# V1_Layout.net
KiCad netlist of a schematic drawn in EAGLE
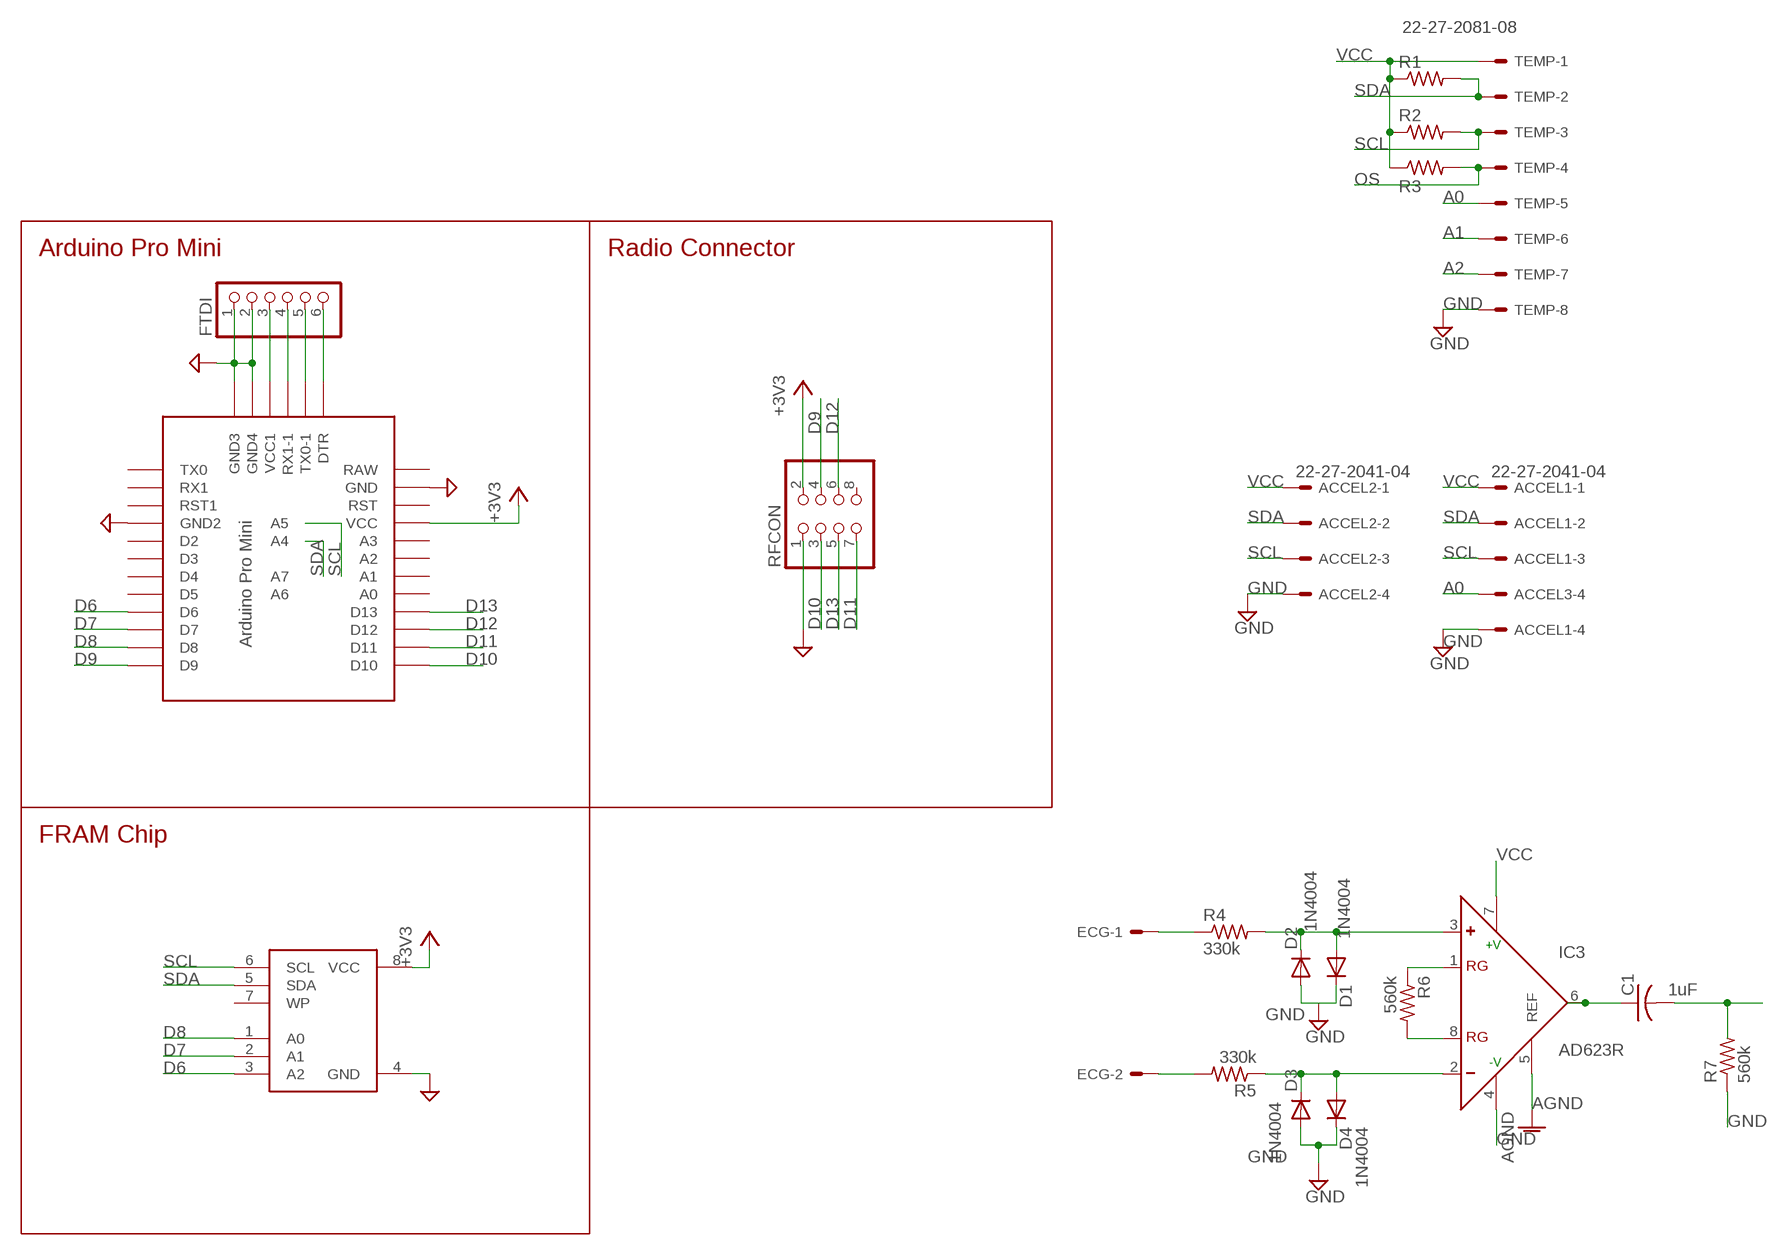
[diagram p0: schematic, sheet 1]

(export (version "E")
  (design (tool "Eeschema 10.0.6"))
  (components
    (comp (ref "ACCEL1")
      (value "22-27-2041-04")
      (footprint "eagle-import:6410-04")
      (fields (field (name "MF") "MOLEX"))
      (libsource (lib "eagle-import") (part "22-?-0427-2041"))
    )
    (comp (ref "ACCEL2")
      (value "22-27-2041-04")
      (footprint "eagle-import:6410-04")
      (fields (field (name "MF") "MOLEX"))
      (libsource (lib "eagle-import") (part "22-?-0427-2041"))
    )
    (comp (ref "ACCEL3")
      (value "22-27-2041-04")
      (footprint "eagle-import:6410-04")
      (fields (field (name "MF") "MOLEX"))
      (libsource (lib "eagle-import") (part "22-?-0427-2041"))
    )
    (comp (ref "C1")
      (value "1uF")
      (footprint "eagle-import:C0805")
      (libsource (lib "eagle-import") (part "C-USC0805"))
    )
    (comp (ref "D1")
      (value "1N4004")
      (footprint "eagle-import:DO41-10")
      (libsource (lib "eagle-import") (part "1N4004"))
    )
    (comp (ref "D2")
      (value "1N4004")
      (footprint "eagle-import:DO41-10")
      (libsource (lib "eagle-import") (part "1N4004"))
    )
    (comp (ref "D3")
      (value "1N4004")
      (footprint "eagle-import:DO41-10")
      (libsource (lib "eagle-import") (part "1N4004"))
    )
    (comp (ref "D4")
      (value "1N4004")
      (footprint "eagle-import:DO41-10")
      (libsource (lib "eagle-import") (part "1N4004"))
    )
    (comp (ref "ECG")
      (value "22-27-2021-02")
      (footprint "eagle-import:6410-02")
      (fields (field (name "MF") "MOLEX"))
      (libsource (lib "eagle-import") (part "22-?-0227-2021"))
    )
    (comp (ref "FTDI")
      (value "PINHD-1X6")
      (footprint "eagle-import:1X06")
      (libsource (lib "eagle-import") (part "PINHD-1X6"))
    )
    (comp (ref "IC3")
      (value "AD623R")
      (footprint "eagle-import:SO8")
      (fields (field (name "MPN") "AD623ARZ."))
      (libsource (lib "eagle-import") (part "AD623R"))
    )
    (comp (ref "R1")
      (value "R-US_R0805")
      (footprint "eagle-import:R0805")
      (libsource (lib "eagle-import") (part "R-US_R0805"))
    )
    (comp (ref "R2")
      (value "R-US_R0805")
      (footprint "eagle-import:R0805")
      (libsource (lib "eagle-import") (part "R-US_R0805"))
    )
    (comp (ref "R3")
      (value "R-US_R0805")
      (footprint "eagle-import:R0805")
      (libsource (lib "eagle-import") (part "R-US_R0805"))
    )
    (comp (ref "R4")
      (value "330k")
      (footprint "eagle-import:R0805")
      (libsource (lib "eagle-import") (part "R-US_R0805"))
    )
    (comp (ref "R5")
      (value "330k")
      (footprint "eagle-import:R0805")
      (libsource (lib "eagle-import") (part "R-US_R0805"))
    )
    (comp (ref "R6")
      (value "560k")
      (footprint "eagle-import:R0805")
      (libsource (lib "eagle-import") (part "R-US_R0805"))
    )
    (comp (ref "R7")
      (value "560k")
      (footprint "eagle-import:R0805")
      (libsource (lib "eagle-import") (part "R-US_R0805"))
    )
    (comp (ref "RFCON")
      (value "PINHD-2X4")
      (footprint "eagle-import:2X04")
      (libsource (lib "eagle-import") (part "PINHD-2X4"))
    )
    (comp (ref "TEMP")
      (value "22-27-2081-08")
      (footprint "eagle-import:6410-08")
      (fields (field (name "MF") "MOLEX"))
      (libsource (lib "eagle-import") (part "22-?-0827-2081"))
    )
    (comp (ref "U$1")
      (value "PRO-MINI-2")
      (footprint "eagle-import:PRO-MINI-2")
      (libsource (lib "eagle-import") (part "PRO-MINI-2"))
    )
    (comp (ref "U2")
      (value "MB85RC256VPF-G-JNERE2")
      (footprint "eagle-import:SOIC8")
      (libsource (lib "eagle-import") (part "MB85RC256VPF-G-JNERE2"))
    )
  )
  (nets
    (net (code "1") (name "+3V3") (class "Default")
      (node (ref "RFCON") (pin "2") (pinfunction "2_2") (pintype "passive"))
      (node (ref "U$1") (pin "VCC") (pinfunction "VCC_VCC") (pintype "bidirectional"))
      (node (ref "U2") (pin "8") (pinfunction "VCC_8") (pintype "bidirectional"))
    )
    (net (code "2") (name "/A0") (class "Default")
      (node (ref "ACCEL3") (pin "4") (pinfunction "S_4") (pintype "passive"))
      (node (ref "TEMP") (pin "5") (pinfunction "S_5") (pintype "passive"))
    )
    (net (code "3") (name "/A1") (class "Default")
      (node (ref "TEMP") (pin "6") (pinfunction "S_6") (pintype "passive"))
    )
    (net (code "4") (name "/A2") (class "Default")
      (node (ref "TEMP") (pin "7") (pinfunction "S_7") (pintype "passive"))
    )
    (net (code "5") (name "/D6") (class "Default")
      (node (ref "U$1") (pin "D6") (pinfunction "D6_D6") (pintype "bidirectional"))
      (node (ref "U2") (pin "3") (pinfunction "A2_3") (pintype "bidirectional"))
    )
    (net (code "6") (name "/D7") (class "Default")
      (node (ref "U$1") (pin "D7") (pinfunction "D7_D7") (pintype "bidirectional"))
      (node (ref "U2") (pin "2") (pinfunction "A1_2") (pintype "bidirectional"))
    )
    (net (code "7") (name "/D8") (class "Default")
      (node (ref "U$1") (pin "D8") (pinfunction "D8_D8") (pintype "bidirectional"))
      (node (ref "U2") (pin "1") (pinfunction "A0_1") (pintype "bidirectional"))
    )
    (net (code "8") (name "/D9") (class "Default")
      (node (ref "RFCON") (pin "4") (pinfunction "4_4") (pintype "passive"))
      (node (ref "U$1") (pin "D9") (pinfunction "D9_D9") (pintype "bidirectional"))
    )
    (net (code "9") (name "/D10") (class "Default")
      (node (ref "RFCON") (pin "3") (pinfunction "3_3") (pintype "passive"))
      (node (ref "U$1") (pin "D10") (pinfunction "D10_D10") (pintype "bidirectional"))
    )
    (net (code "10") (name "/D11") (class "Default")
      (node (ref "RFCON") (pin "7") (pinfunction "7_7") (pintype "passive"))
      (node (ref "U$1") (pin "D11") (pinfunction "D11_D11") (pintype "bidirectional"))
    )
    (net (code "11") (name "/D12") (class "Default")
      (node (ref "RFCON") (pin "6") (pinfunction "6_6") (pintype "passive"))
      (node (ref "U$1") (pin "D12") (pinfunction "D12_D12") (pintype "bidirectional"))
    )
    (net (code "12") (name "/D13") (class "Default")
      (node (ref "RFCON") (pin "5") (pinfunction "5_5") (pintype "passive"))
      (node (ref "U$1") (pin "D13") (pinfunction "D13_D13") (pintype "bidirectional"))
    )
    (net (code "13") (name "/OS") (class "Default")
      (node (ref "R3") (pin "2") (pinfunction "2_2") (pintype "passive"))
      (node (ref "TEMP") (pin "4") (pinfunction "S_4") (pintype "passive"))
    )
    (net (code "14") (name "/SCL") (class "Default")
      (node (ref "ACCEL1") (pin "3") (pinfunction "S_3") (pintype "passive"))
      (node (ref "ACCEL2") (pin "3") (pinfunction "S_3") (pintype "passive"))
      (node (ref "R2") (pin "2") (pinfunction "2_2") (pintype "passive"))
      (node (ref "TEMP") (pin "3") (pinfunction "S_3") (pintype "passive"))
      (node (ref "U$1") (pin "A5") (pinfunction "A5_A5") (pintype "bidirectional"))
      (node (ref "U2") (pin "6") (pinfunction "SCL_6") (pintype "bidirectional"))
    )
    (net (code "15") (name "/SDA") (class "Default")
      (node (ref "ACCEL1") (pin "2") (pinfunction "S_2") (pintype "passive"))
      (node (ref "ACCEL2") (pin "2") (pinfunction "S_2") (pintype "passive"))
      (node (ref "R1") (pin "2") (pinfunction "2_2") (pintype "passive"))
      (node (ref "TEMP") (pin "2") (pinfunction "S_2") (pintype "passive"))
      (node (ref "U$1") (pin "A4") (pinfunction "A4_A4") (pintype "bidirectional"))
      (node (ref "U2") (pin "5") (pinfunction "SDA_5") (pintype "bidirectional"))
    )
    (net (code "16") (name "/VCC") (class "Default")
      (node (ref "ACCEL1") (pin "1") (pinfunction "S_1") (pintype "passive"))
      (node (ref "ACCEL2") (pin "1") (pinfunction "S_1") (pintype "passive"))
      (node (ref "IC3") (pin "7") (pinfunction "+V_7") (pintype "power_in"))
      (node (ref "R1") (pin "1") (pinfunction "1_1") (pintype "passive"))
      (node (ref "R2") (pin "1") (pinfunction "1_1") (pintype "passive"))
      (node (ref "R3") (pin "1") (pinfunction "1_1") (pintype "passive"))
      (node (ref "TEMP") (pin "1") (pinfunction "S_1") (pintype "passive"))
    )
    (net (code "17") (name "AGND") (class "Default")
      (node (ref "IC3") (pin "5") (pinfunction "REF_5") (pintype "passive"))
    )
    (net (code "18") (name "GND") (class "Default")
      (node (ref "ACCEL1") (pin "4") (pinfunction "S_4") (pintype "passive"))
      (node (ref "ACCEL2") (pin "4") (pinfunction "S_4") (pintype "passive"))
      (node (ref "C1") (pin "2") (pinfunction "2_2") (pintype "passive"))
      (node (ref "D1") (pin "C") (pinfunction "C_C") (pintype "passive"))
      (node (ref "D2") (pin "A") (pinfunction "A_A") (pintype "passive"))
      (node (ref "D3") (pin "A") (pinfunction "A_A") (pintype "passive"))
      (node (ref "D4") (pin "C") (pinfunction "C_C") (pintype "passive"))
      (node (ref "FTDI") (pin "1") (pinfunction "1_1") (pintype "passive"))
      (node (ref "FTDI") (pin "2") (pinfunction "2_2") (pintype "passive"))
      (node (ref "IC3") (pin "4") (pinfunction "-V_4") (pintype "power_in"))
      (node (ref "R7") (pin "1") (pinfunction "1_1") (pintype "passive"))
      (node (ref "R7") (pin "2") (pinfunction "2_2") (pintype "passive"))
      (node (ref "RFCON") (pin "1") (pinfunction "1_1") (pintype "passive"))
      (node (ref "TEMP") (pin "8") (pinfunction "S_8") (pintype "passive"))
      (node (ref "U$1") (pin "GND") (pinfunction "GND_GND") (pintype "bidirectional"))
      (node (ref "U$1") (pin "GND1") (pinfunction "GND2_GND1") (pintype "bidirectional"))
      (node (ref "U$1") (pin "GND2") (pinfunction "GND3_GND2") (pintype "bidirectional"))
      (node (ref "U$1") (pin "GND3") (pinfunction "GND4_GND3") (pintype "bidirectional"))
      (node (ref "U2") (pin "4") (pinfunction "GND_4") (pintype "bidirectional"))
    )
    (net (code "19") (name "Net-(ECGA-S)") (class "Default")
      (node (ref "ECG") (pin "1") (pinfunction "S_1") (pintype "passive"))
      (node (ref "R4") (pin "1") (pinfunction "1_1") (pintype "passive"))
    )
    (net (code "20") (name "Net-(ECGB-S)") (class "Default")
      (node (ref "ECG") (pin "2") (pinfunction "S_2") (pintype "passive"))
      (node (ref "R5") (pin "2") (pinfunction "2_2") (pintype "passive"))
    )
    (net (code "21") (name "Net-(FTDI-Pad3)") (class "Default")
      (node (ref "FTDI") (pin "3") (pinfunction "3_3") (pintype "passive"))
      (node (ref "U$1") (pin "VCC1") (pinfunction "VCC1_VCC1") (pintype "bidirectional"))
    )
    (net (code "22") (name "Net-(FTDI-Pad4)") (class "Default")
      (node (ref "FTDI") (pin "4") (pinfunction "4_4") (pintype "passive"))
      (node (ref "U$1") (pin "RX1-1") (pinfunction "RX1-1_RX1-1") (pintype "bidirectional"))
    )
    (net (code "23") (name "Net-(FTDI-Pad5)") (class "Default")
      (node (ref "FTDI") (pin "5") (pinfunction "5_5") (pintype "passive"))
      (node (ref "U$1") (pin "TX0-1") (pinfunction "TX0-1_TX0-1") (pintype "bidirectional"))
    )
    (net (code "24") (name "Net-(FTDI-Pad6)") (class "Default")
      (node (ref "FTDI") (pin "6") (pinfunction "6_6") (pintype "passive"))
      (node (ref "U$1") (pin "DTR") (pinfunction "DTR_DTR") (pintype "bidirectional"))
    )
    (net (code "25") (name "Net-(IC3-+)") (class "Default")
      (node (ref "D1") (pin "A") (pinfunction "A_A") (pintype "passive"))
      (node (ref "D2") (pin "C") (pinfunction "C_C") (pintype "passive"))
      (node (ref "IC3") (pin "3") (pinfunction "+_3") (pintype "input"))
      (node (ref "R4") (pin "2") (pinfunction "2_2") (pintype "passive"))
    )
    (net (code "26") (name "Net-(IC3--)") (class "Default")
      (node (ref "D3") (pin "C") (pinfunction "C_C") (pintype "passive"))
      (node (ref "D4") (pin "A") (pinfunction "A_A") (pintype "passive"))
      (node (ref "IC3") (pin "2") (pinfunction "-_2") (pintype "input"))
      (node (ref "R5") (pin "1") (pinfunction "1_1") (pintype "passive"))
    )
    (net (code "27") (name "Net-(IC3-OUT)") (class "Default")
      (node (ref "C1") (pin "1") (pinfunction "1_1") (pintype "passive"))
      (node (ref "IC3") (pin "6") (pinfunction "OUT_6") (pintype "output"))
    )
    (net (code "28") (name "Net-(IC3-RG-Pad1)") (class "Default")
      (node (ref "IC3") (pin "1") (pinfunction "RG_1") (pintype "passive"))
      (node (ref "R6") (pin "1") (pinfunction "1_1") (pintype "passive"))
    )
    (net (code "29") (name "Net-(IC3-RG-Pad8)") (class "Default")
      (node (ref "IC3") (pin "8") (pinfunction "RG_8") (pintype "passive"))
      (node (ref "R6") (pin "2") (pinfunction "2_2") (pintype "passive"))
    )
    (net (code "30") (name "unconnected-(RFCON-Pad8)") (class "Default")
      (node (ref "RFCON") (pin "8") (pinfunction "8_8") (pintype "passive"))
    )
    (net (code "31") (name "unconnected-(U$1-PadA0)") (class "Default")
      (node (ref "U$1") (pin "A0") (pinfunction "A0_A0") (pintype "bidirectional"))
    )
    (net (code "32") (name "unconnected-(U$1-PadA1)") (class "Default")
      (node (ref "U$1") (pin "A1") (pinfunction "A1_A1") (pintype "bidirectional"))
    )
    (net (code "33") (name "unconnected-(U$1-PadA2)") (class "Default")
      (node (ref "U$1") (pin "A2") (pinfunction "A2_A2") (pintype "bidirectional"))
    )
    (net (code "34") (name "unconnected-(U$1-PadA3)") (class "Default")
      (node (ref "U$1") (pin "A3") (pinfunction "A3_A3") (pintype "bidirectional"))
    )
    (net (code "35") (name "unconnected-(U$1-PadA6)") (class "Default")
      (node (ref "U$1") (pin "A6") (pinfunction "A6_A6") (pintype "bidirectional"))
    )
    (net (code "36") (name "unconnected-(U$1-PadA7)") (class "Default")
      (node (ref "U$1") (pin "A7") (pinfunction "A7_A7") (pintype "bidirectional"))
    )
    (net (code "37") (name "unconnected-(U$1-PadD2)") (class "Default")
      (node (ref "U$1") (pin "D2") (pinfunction "D2_D2") (pintype "bidirectional"))
    )
    (net (code "38") (name "unconnected-(U$1-PadD3)") (class "Default")
      (node (ref "U$1") (pin "D3") (pinfunction "D3_D3") (pintype "bidirectional"))
    )
    (net (code "39") (name "unconnected-(U$1-PadD4)") (class "Default")
      (node (ref "U$1") (pin "D4") (pinfunction "D4_D4") (pintype "bidirectional"))
    )
    (net (code "40") (name "unconnected-(U$1-PadD5)") (class "Default")
      (node (ref "U$1") (pin "D5") (pinfunction "D5_D5") (pintype "bidirectional"))
    )
    (net (code "41") (name "unconnected-(U$1-PadRAW)") (class "Default")
      (node (ref "U$1") (pin "RAW") (pinfunction "RAW_RAW") (pintype "bidirectional"))
    )
    (net (code "42") (name "unconnected-(U$1-PadRST)") (class "Default")
      (node (ref "U$1") (pin "RST") (pinfunction "RST_RST") (pintype "bidirectional"))
    )
    (net (code "43") (name "unconnected-(U$1-PadRST1)") (class "Default")
      (node (ref "U$1") (pin "RST1") (pinfunction "RST1_RST1") (pintype "bidirectional"))
    )
    (net (code "44") (name "unconnected-(U$1-PadRX1)") (class "Default")
      (node (ref "U$1") (pin "RX1") (pinfunction "RX1_RX1") (pintype "bidirectional"))
    )
    (net (code "45") (name "unconnected-(U$1-PadTX0)") (class "Default")
      (node (ref "U$1") (pin "TX0") (pinfunction "TX0_TX0") (pintype "bidirectional"))
    )
    (net (code "46") (name "unconnected-(U2-WP-Pad7)") (class "Default")
      (node (ref "U2") (pin "7") (pinfunction "WP_7") (pintype "bidirectional"))
    )
  )
)
